# tap.net
KiCad netlist of a schematic drawn in EAGLE
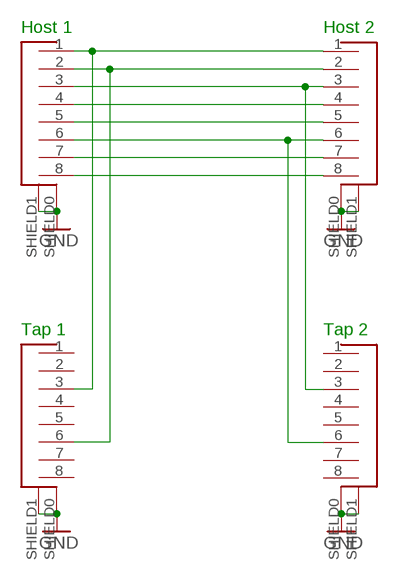
[diagram p0: schematic, sheet 1]

(export (version "E")
  (design (tool "Eeschema 10.0.6"))
  (components
    (comp (ref "HOST1")
      (value "451000")
      (footprint "eagle-import:RJ45")
      (libsource (lib "eagle-import") (part "451000"))
    )
    (comp (ref "HOST2")
      (value "451000")
      (footprint "eagle-import:RJ45")
      (libsource (lib "eagle-import") (part "451000"))
    )
    (comp (ref "TAP1")
      (value "451000")
      (footprint "eagle-import:RJ45")
      (libsource (lib "eagle-import") (part "451000"))
    )
    (comp (ref "TAP2")
      (value "451000")
      (footprint "eagle-import:RJ45")
      (libsource (lib "eagle-import") (part "451000"))
    )
  )
  (nets
    (net (code "1") (name "GND") (class "Default")
      (node (ref "HOST1") (pin "SHIELD0") (pinfunction "SHIELD0_SHIELD0") (pintype "bidirectional"))
      (node (ref "HOST1") (pin "SHIELD1") (pinfunction "SHIELD1_SHIELD1") (pintype "bidirectional"))
      (node (ref "HOST2") (pin "SHIELD0") (pinfunction "SHIELD0_SHIELD0") (pintype "bidirectional"))
      (node (ref "HOST2") (pin "SHIELD1") (pinfunction "SHIELD1_SHIELD1") (pintype "bidirectional"))
      (node (ref "TAP1") (pin "SHIELD0") (pinfunction "SHIELD0_SHIELD0") (pintype "bidirectional"))
      (node (ref "TAP1") (pin "SHIELD1") (pinfunction "SHIELD1_SHIELD1") (pintype "bidirectional"))
      (node (ref "TAP2") (pin "SHIELD0") (pinfunction "SHIELD0_SHIELD0") (pintype "bidirectional"))
      (node (ref "TAP2") (pin "SHIELD1") (pinfunction "SHIELD1_SHIELD1") (pintype "bidirectional"))
    )
    (net (code "2") (name "Net-(HOST1-Pad1)") (class "Default")
      (node (ref "HOST1") (pin "1") (pinfunction "1_1") (pintype "bidirectional"))
      (node (ref "HOST2") (pin "1") (pinfunction "1_1") (pintype "bidirectional"))
      (node (ref "TAP1") (pin "3") (pinfunction "3_3") (pintype "bidirectional"))
    )
    (net (code "3") (name "Net-(HOST1-Pad2)") (class "Default")
      (node (ref "HOST1") (pin "2") (pinfunction "2_2") (pintype "bidirectional"))
      (node (ref "HOST2") (pin "2") (pinfunction "2_2") (pintype "bidirectional"))
      (node (ref "TAP1") (pin "6") (pinfunction "6_6") (pintype "bidirectional"))
    )
    (net (code "4") (name "Net-(HOST1-Pad3)") (class "Default")
      (node (ref "HOST1") (pin "3") (pinfunction "3_3") (pintype "bidirectional"))
      (node (ref "HOST2") (pin "3") (pinfunction "3_3") (pintype "bidirectional"))
      (node (ref "TAP2") (pin "3") (pinfunction "3_3") (pintype "bidirectional"))
    )
    (net (code "5") (name "Net-(HOST1-Pad4)") (class "Default")
      (node (ref "HOST1") (pin "4") (pinfunction "4_4") (pintype "bidirectional"))
      (node (ref "HOST2") (pin "4") (pinfunction "4_4") (pintype "bidirectional"))
    )
    (net (code "6") (name "Net-(HOST1-Pad5)") (class "Default")
      (node (ref "HOST1") (pin "5") (pinfunction "5_5") (pintype "bidirectional"))
      (node (ref "HOST2") (pin "5") (pinfunction "5_5") (pintype "bidirectional"))
    )
    (net (code "7") (name "Net-(HOST1-Pad6)") (class "Default")
      (node (ref "HOST1") (pin "6") (pinfunction "6_6") (pintype "bidirectional"))
      (node (ref "HOST2") (pin "6") (pinfunction "6_6") (pintype "bidirectional"))
      (node (ref "TAP2") (pin "6") (pinfunction "6_6") (pintype "bidirectional"))
    )
    (net (code "8") (name "Net-(HOST1-Pad7)") (class "Default")
      (node (ref "HOST1") (pin "7") (pinfunction "7_7") (pintype "bidirectional"))
      (node (ref "HOST2") (pin "7") (pinfunction "7_7") (pintype "bidirectional"))
    )
    (net (code "9") (name "Net-(HOST1-Pad8)") (class "Default")
      (node (ref "HOST1") (pin "8") (pinfunction "8_8") (pintype "bidirectional"))
      (node (ref "HOST2") (pin "8") (pinfunction "8_8") (pintype "bidirectional"))
    )
    (net (code "10") (name "unconnected-(TAP1-Pad1)") (class "Default")
      (node (ref "TAP1") (pin "1") (pinfunction "1_1") (pintype "bidirectional"))
    )
    (net (code "11") (name "unconnected-(TAP1-Pad2)") (class "Default")
      (node (ref "TAP1") (pin "2") (pinfunction "2_2") (pintype "bidirectional"))
    )
    (net (code "12") (name "unconnected-(TAP1-Pad4)") (class "Default")
      (node (ref "TAP1") (pin "4") (pinfunction "4_4") (pintype "bidirectional"))
    )
    (net (code "13") (name "unconnected-(TAP1-Pad5)") (class "Default")
      (node (ref "TAP1") (pin "5") (pinfunction "5_5") (pintype "bidirectional"))
    )
    (net (code "14") (name "unconnected-(TAP1-Pad7)") (class "Default")
      (node (ref "TAP1") (pin "7") (pinfunction "7_7") (pintype "bidirectional"))
    )
    (net (code "15") (name "unconnected-(TAP1-Pad8)") (class "Default")
      (node (ref "TAP1") (pin "8") (pinfunction "8_8") (pintype "bidirectional"))
    )
    (net (code "16") (name "unconnected-(TAP2-Pad1)") (class "Default")
      (node (ref "TAP2") (pin "1") (pinfunction "1_1") (pintype "bidirectional"))
    )
    (net (code "17") (name "unconnected-(TAP2-Pad2)") (class "Default")
      (node (ref "TAP2") (pin "2") (pinfunction "2_2") (pintype "bidirectional"))
    )
    (net (code "18") (name "unconnected-(TAP2-Pad4)") (class "Default")
      (node (ref "TAP2") (pin "4") (pinfunction "4_4") (pintype "bidirectional"))
    )
    (net (code "19") (name "unconnected-(TAP2-Pad5)") (class "Default")
      (node (ref "TAP2") (pin "5") (pinfunction "5_5") (pintype "bidirectional"))
    )
    (net (code "20") (name "unconnected-(TAP2-Pad7)") (class "Default")
      (node (ref "TAP2") (pin "7") (pinfunction "7_7") (pintype "bidirectional"))
    )
    (net (code "21") (name "unconnected-(TAP2-Pad8)") (class "Default")
      (node (ref "TAP2") (pin "8") (pinfunction "8_8") (pintype "bidirectional"))
    )
  )
)
